# M3.net
KiCad netlist of a schematic drawn in Altium Designer
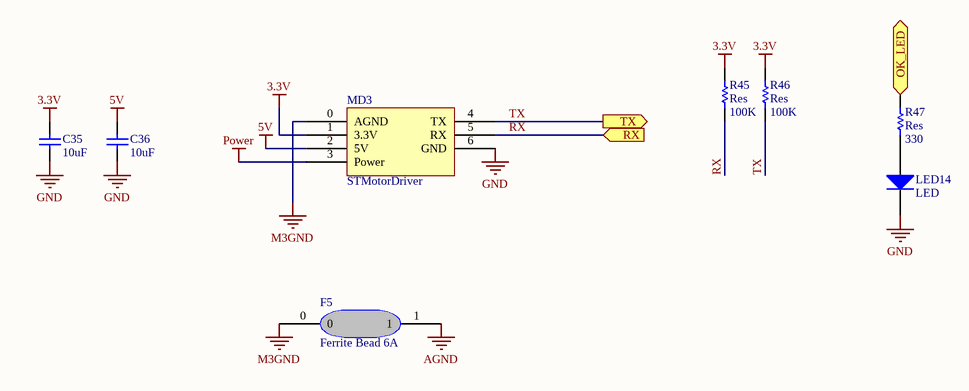
[diagram p0: M3.SchDoc]

(export (version "E")
  (design (tool "Eeschema 10.0.6"))
  (components
    (comp (ref "C35")
      (value "10uF")
      (footprint "2012[0805]")
      (description "Capacitor")
      (fields (field (name "Comment") "Cap_UP") (field (name "PUBLISHER") "Altium Limited"))
      (libsource (lib "KN2CLib") (part "Cap_UP"))
    )
    (comp (ref "C36")
      (value "10uF")
      (footprint "2012[0805]")
      (description "Capacitor")
      (fields (field (name "Comment") "Cap_UP") (field (name "PUBLISHER") "Altium Limited"))
      (libsource (lib "KN2CLib") (part "Cap_UP"))
    )
    (comp (ref "F5")
      (value "Ferrite Bead 6A")
      (footprint "f6A")
      (libsource (lib "Ferrite Bead") (part "F6A"))
    )
    (comp (ref "LED14")
      (value "LED")
      (footprint "2012[0805]")
      (description "1 Amp General Purpose Rectifier")
      (fields (field (name "PUBLISHER") "Altium Limited"))
      (libsource (lib "KN2CLib") (part "Diode"))
    )
    (comp (ref "MD3")
      (value "STMotorDriver")
      (footprint "MotorDriver")
      (libsource (lib "STMotorDriver") (part "STMotorDriver"))
    )
    (comp (ref "R45")
      (value "Res")
      (footprint "2012[0805]")
      (description "Semiconductor Resistor")
      (fields (field (name "ALTIUM_VALUE") "100K") (field (name "PUBLISHER") "Altium Limited"))
      (libsource (lib "KN2CLib") (part "Res"))
    )
    (comp (ref "R46")
      (value "Res")
      (footprint "2012[0805]")
      (description "Semiconductor Resistor")
      (fields (field (name "ALTIUM_VALUE") "100K") (field (name "PUBLISHER") "Altium Limited"))
      (libsource (lib "KN2CLib") (part "Res"))
    )
    (comp (ref "R47")
      (value "Res")
      (footprint "2012[0805]")
      (description "Semiconductor Resistor")
      (fields (field (name "ALTIUM_VALUE") "330") (field (name "PUBLISHER") "Altium Limited"))
      (libsource (lib "KN2CLib") (part "Res"))
    )
  )
  (nets
    (net (code "1") (name "/OK_LED") (class "Default")
      (node (ref "R47") (pin "1") (pinfunction "1_1") (pintype "passive"))
    )
    (net (code "2") (name "/RX") (class "Default")
      (node (ref "MD3") (pin "5") (pinfunction "RX_5") (pintype "passive"))
      (node (ref "R45") (pin "1") (pinfunction "1_1") (pintype "passive"))
    )
    (net (code "3") (name "/TX") (class "Default")
      (node (ref "MD3") (pin "4") (pinfunction "TX_4") (pintype "passive"))
      (node (ref "R46") (pin "1") (pinfunction "1_1") (pintype "passive"))
    )
    (net (code "4") (name "3.3V") (class "Default")
      (node (ref "C35") (pin "2") (pinfunction "2_2") (pintype "passive"))
      (node (ref "MD3") (pin "1") (pinfunction "3.3V_1") (pintype "passive"))
      (node (ref "R45") (pin "2") (pinfunction "2_2") (pintype "passive"))
      (node (ref "R46") (pin "2") (pinfunction "2_2") (pintype "passive"))
    )
    (net (code "5") (name "5V") (class "Default")
      (node (ref "C36") (pin "2") (pinfunction "2_2") (pintype "passive"))
      (node (ref "MD3") (pin "2") (pinfunction "5V_2") (pintype "passive"))
    )
    (net (code "6") (name "AGND") (class "Default")
      (node (ref "F5") (pin "1") (pinfunction "1_1") (pintype "passive"))
    )
    (net (code "7") (name "GND") (class "Default")
      (node (ref "C35") (pin "1") (pinfunction "1_1") (pintype "passive"))
      (node (ref "C36") (pin "1") (pinfunction "1_1") (pintype "passive"))
      (node (ref "LED14") (pin "2") (pinfunction "K_2") (pintype "passive"))
      (node (ref "MD3") (pin "6") (pinfunction "GND_6") (pintype "passive"))
    )
    (net (code "8") (name "M3GND") (class "Default")
      (node (ref "F5") (pin "0") (pinfunction "0_0") (pintype "passive"))
      (node (ref "MD3") (pin "0") (pinfunction "AGND_0") (pintype "passive"))
    )
    (net (code "9") (name "Net-(LED14-A)") (class "Default")
      (node (ref "LED14") (pin "1") (pinfunction "A_1") (pintype "passive"))
      (node (ref "R47") (pin "2") (pinfunction "2_2") (pintype "passive"))
    )
    (net (code "10") (name "Power") (class "Default")
      (node (ref "MD3") (pin "3") (pinfunction "Power_3") (pintype "passive"))
    )
  )
)
